# DS_zk.net
KiCad netlist of a schematic drawn in Altium Designer
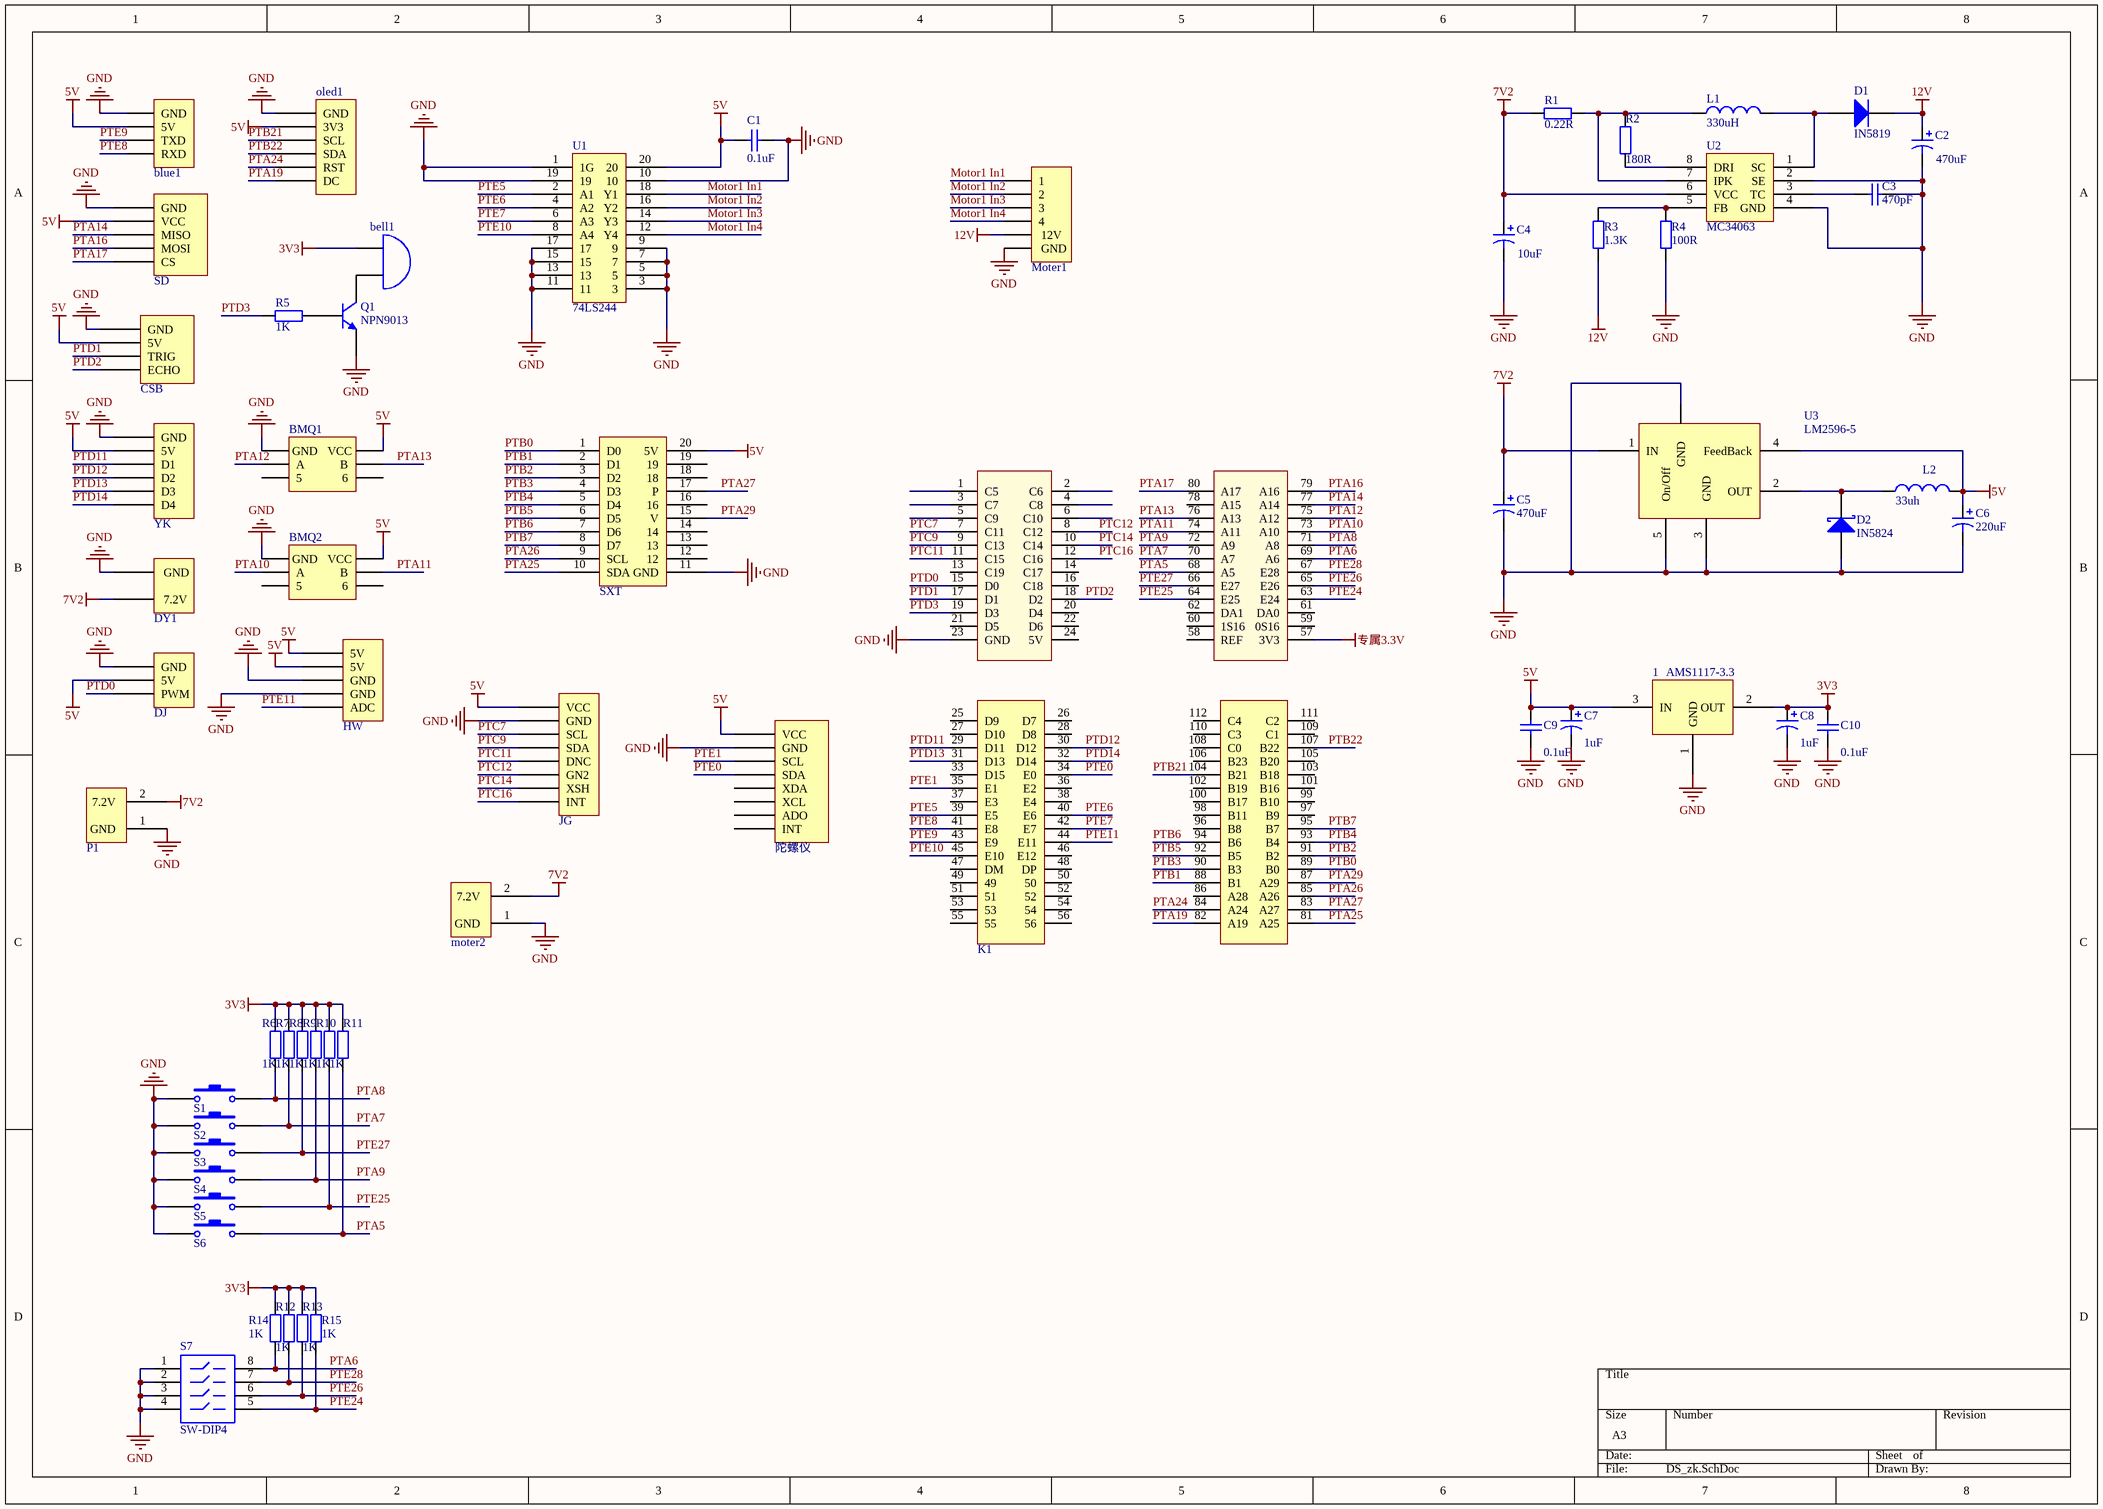
[diagram p0: DS_zk.SchDoc]

(export (version "E")
  (design (tool "Eeschema 10.0.6"))
  (components
    (comp (ref "*1") (value "SD") (footprint "HDR1X5 - duplicate") (libsource (lib "DS_zk") (part "SD卡")))
    (comp (ref "*2") (value "CSB") (footprint "HDR1X4") (libsource (lib "DS_zk") (part "超声波")))
    (comp (ref "*3") (value "YK") (footprint "HDR1X6") (libsource (lib "DS_zk") (part "遥控")))
    (comp (ref "*4") (value "SXT") (footprint "摄像头") (libsource (lib "DS_zk") (part "摄像头")))
    (comp (ref "*5") (value "HW") (footprint "HDR1X5") (libsource (lib "DS_zk") (part "红外测距")))
    (comp (ref "*6") (value "DJ") (footprint "HDR1X3") (libsource (lib "DS_zk") (part "舵机")))
    (comp (ref "*7") (value "JG") (footprint "HDR1X8") (libsource (lib "DS_zk") (part "激光")))
    (comp (ref "*8") (value "陀螺仪") (footprint "HDR1X8") (libsource (lib "DS_zk") (part "陀螺仪")))
    (comp (ref "1")
      (value "AMS1117-3.3")
      (footprint "lm1117-5v")
      (libsource (lib "红牛板Schlib") (part "LT1117-3.3"))
    )
    (comp (ref "bell1")
      (value "Bell")
      (footprint "bezzer")
      (description "Electrical Bell")
      (fields (field (name "PUBLISHER") "Altium Limited"))
      (libsource (lib "Miscellaneous Devices") (part "Bell"))
    )
    (comp (ref "blue1")
      (value "blueteeth2")
      (footprint "HDR1X4")
      (libsource (lib "DS_zk") (part "blueteeth"))
    )
    (comp (ref "BMQ1") (value "encode_1") (footprint "HDR2X3") (libsource (lib "主控板原理图") (part "encode")))
    (comp (ref "BMQ2") (value "encode_2") (footprint "HDR2X3") (libsource (lib "主控板原理图") (part "encode")))
    (comp (ref "C1")
      (value "0.1uF")
      (footprint "0603")
      (description "Capacitor (Semiconductor SIM Model)")
      (fields (field (name "PUBLISHER") "Altium Limited"))
      (libsource (lib "Miscellaneous Devices") (part "Cap Semi"))
    )
    (comp (ref "C2")
      (value "470uF")
      (footprint "470UF")
      (description "Polarized Capacitor (Surface Mount)")
      (fields (field (name "PUBLISHER") "Altium Limited"))
      (libsource (lib "Miscellaneous Devices") (part "Cap Pol3"))
    )
    (comp (ref "C3")
      (value "470pF")
      (footprint "0805")
      (description "Capacitor (Semiconductor SIM Model)")
      (fields (field (name "PUBLISHER") "Altium Limited"))
      (libsource (lib "Miscellaneous Devices") (part "Cap Semi"))
    )
    (comp (ref "C4")
      (value "10uF")
      (footprint "0805")
      (description "Polarized Capacitor (Surface Mount)")
      (fields (field (name "PUBLISHER") "Altium Limited"))
      (libsource (lib "Miscellaneous Devices") (part "Cap Pol3"))
    )
    (comp (ref "C5")
      (value "470uF")
      (footprint "470uf")
      (description "Polarized Capacitor (Radial)")
      (fields (field (name "Comment") "Cap Pol1") (field (name "PUBLISHER") "Altium Limited"))
      (libsource (lib "主控板原理图") (part "Cap Pol1"))
    )
    (comp (ref "C6")
      (value "220uF")
      (footprint "220uf")
      (description "Polarized Capacitor (Radial)")
      (fields (field (name "Comment") "Cap Pol1") (field (name "PUBLISHER") "Altium Limited"))
      (libsource (lib "主控板原理图") (part "Cap Pol1"))
    )
    (comp (ref "C7")
      (value "1uF")
      (footprint "0805")
      (description "Polarized Capacitor (Radial)")
      (fields (field (name "Comment") "Cap Pol1") (field (name "PUBLISHER") "Altium Limited"))
      (libsource (lib "Miscellaneous Devices") (part "Cap Pol1"))
    )
    (comp (ref "C8")
      (value "1uF")
      (footprint "0805")
      (description "Polarized Capacitor (Radial)")
      (fields (field (name "Comment") "Cap Pol1") (field (name "PUBLISHER") "Altium Limited"))
      (libsource (lib "Miscellaneous Devices") (part "Cap Pol1"))
    )
    (comp (ref "C9")
      (value "0.1uF")
      (footprint "0805")
      (description "Capacitor")
      (fields (field (name "Comment") "Cap") (field (name "PUBLISHER") "Altium Limited"))
      (libsource (lib "Miscellaneous Devices") (part "Cap"))
    )
    (comp (ref "C10")
      (value "0.1uF")
      (footprint "0805")
      (description "Capacitor")
      (fields (field (name "Comment") "Cap") (field (name "PUBLISHER") "Altium Limited"))
      (libsource (lib "Miscellaneous Devices") (part "Cap"))
    )
    (comp (ref "D1")
      (value "IN5819")
      (footprint "0805LED")
      (description "Default Diode")
      (fields (field (name "PUBLISHER") "Altium Limited"))
      (libsource (lib "Miscellaneous Devices") (part "Diode"))
    )
    (comp (ref "D2") (value "IN5824") (footprint "1N5824") (libsource (lib "主控板原理图") (part "IN5824")))
    (comp (ref "DY1") (value "H1") (footprint "HDR1X2") (libsource (lib "DS_zk") (part "H1")))
    (comp (ref "K1") (value "K60") (footprint "DS_K60") (libsource (lib "DS_zk") (part "K60")))
    (comp (ref "L1")
      (value "330uH")
      (footprint "电感8*8")
      (description "Inductor")
      (fields (field (name "PUBLISHER") "Altium Limited"))
      (libsource (lib "Miscellaneous Devices") (part "Inductor"))
    )
    (comp (ref "L2")
      (value "33uh")
      (footprint "电感8*8")
      (description "Inductor")
      (fields (field (name "PUBLISHER") "Altium Limited"))
      (libsource (lib "主控板原理图") (part "Inductor"))
    )
    (comp (ref "Moter1") (value "Motor") (footprint "HDR1X6") (libsource (lib "DS_zk") (part "Motor")))
    (comp (ref "moter2") (value "H1") (footprint "KF301-2P") (libsource (lib "主控板原理图") (part "H1")))
    (comp (ref "oled1") (value "OLED") (footprint "HDR1X6") (libsource (lib "LY") (part "OLED")))
    (comp (ref "P1") (value "H1") (footprint "KF301-2P") (libsource (lib "主控板原理图") (part "H1")))
    (comp (ref "Q1")
      (value "NPN9013")
      (footprint "npn9013")
      (description "NPN General Purpose Amplifier")
      (fields (field (name "PUBLISHER") "Altium Limited"))
      (libsource (lib "Miscellaneous Devices") (part "2N3904"))
    )
    (comp (ref "R1")
      (value "0.22R")
      (footprint "0805")
      (description "Resistor")
      (fields (field (name "PUBLISHER") "Altium Limited"))
      (libsource (lib "") (part "Res2_1"))
    )
    (comp (ref "R2")
      (value "180R")
      (footprint "0805")
      (description "Resistor")
      (fields (field (name "PUBLISHER") "Altium Limited"))
      (libsource (lib "Miscellaneous Devices") (part "Res2"))
    )
    (comp (ref "R3")
      (value "1.3K")
      (footprint "0805")
      (description "Resistor")
      (fields (field (name "PUBLISHER") "Altium Limited"))
      (libsource (lib "") (part "Res2_2"))
    )
    (comp (ref "R4")
      (value "100R")
      (footprint "0805")
      (description "Resistor")
      (fields (field (name "PUBLISHER") "Altium Limited"))
      (libsource (lib "") (part "Res2_2"))
    )
    (comp (ref "R5")
      (value "1K")
      (footprint "0805")
      (description "Resistor")
      (fields (field (name "Comment") "Res2") (field (name "PUBLISHER") "Altium Limited"))
      (libsource (lib "") (part "Res2_1"))
    )
    (comp (ref "R6")
      (value "1K")
      (footprint "0805")
      (description "Resistor")
      (fields (field (name "Comment") "Res2") (field (name "PUBLISHER") "Altium Limited"))
      (libsource (lib "主控板原理图") (part "Res2"))
    )
    (comp (ref "R7")
      (value "1K")
      (footprint "0805")
      (description "Resistor")
      (fields (field (name "Comment") "Res2") (field (name "PUBLISHER") "Altium Limited"))
      (libsource (lib "主控板原理图") (part "Res2"))
    )
    (comp (ref "R8")
      (value "1K")
      (footprint "0805")
      (description "Resistor")
      (fields (field (name "Comment") "Res2") (field (name "PUBLISHER") "Altium Limited"))
      (libsource (lib "主控板原理图") (part "Res2"))
    )
    (comp (ref "R9")
      (value "1K")
      (footprint "0805")
      (description "Resistor")
      (fields (field (name "Comment") "Res2") (field (name "PUBLISHER") "Altium Limited"))
      (libsource (lib "主控板原理图") (part "Res2"))
    )
    (comp (ref "R10")
      (value "1K")
      (footprint "0805")
      (description "Resistor")
      (fields (field (name "Comment") "Res2") (field (name "PUBLISHER") "Altium Limited"))
      (libsource (lib "主控板原理图") (part "Res2"))
    )
    (comp (ref "R11")
      (value "1K")
      (footprint "0805")
      (description "Resistor")
      (fields (field (name "Comment") "Res2") (field (name "PUBLISHER") "Altium Limited"))
      (libsource (lib "主控板原理图") (part "Res2"))
    )
    (comp (ref "R12")
      (value "1K")
      (footprint "0805")
      (description "Resistor")
      (fields (field (name "Comment") "Res2") (field (name "PUBLISHER") "Altium Limited"))
      (libsource (lib "主控板原理图") (part "Res2"))
    )
    (comp (ref "R13")
      (value "1K")
      (footprint "0805")
      (description "Resistor")
      (fields (field (name "Comment") "Res2") (field (name "PUBLISHER") "Altium Limited"))
      (libsource (lib "主控板原理图") (part "Res2"))
    )
    (comp (ref "R14")
      (value "1K")
      (footprint "0805")
      (description "Resistor")
      (fields (field (name "Comment") "Res2") (field (name "PUBLISHER") "Altium Limited"))
      (libsource (lib "主控板原理图") (part "Res2"))
    )
    (comp (ref "R15")
      (value "1K")
      (footprint "0805")
      (description "Resistor")
      (fields (field (name "Comment") "Res2") (field (name "PUBLISHER") "Altium Limited"))
      (libsource (lib "主控板原理图") (part "Res2"))
    )
    (comp (ref "S1")
      (value "SW-PB")
      (footprint "BUTTON")
      (description "Switch")
      (fields (field (name "PUBLISHER") "Altium Limited"))
      (libsource (lib "主控板原理图") (part "SW-PB"))
    )
    (comp (ref "S2")
      (value "SW-PB")
      (footprint "BUTTON")
      (description "Switch")
      (fields (field (name "PUBLISHER") "Altium Limited"))
      (libsource (lib "主控板原理图") (part "SW-PB"))
    )
    (comp (ref "S3")
      (value "SW-PB")
      (footprint "BUTTON")
      (description "Switch")
      (fields (field (name "PUBLISHER") "Altium Limited"))
      (libsource (lib "主控板原理图") (part "SW-PB"))
    )
    (comp (ref "S4")
      (value "SW-PB")
      (footprint "BUTTON")
      (description "Switch")
      (fields (field (name "PUBLISHER") "Altium Limited"))
      (libsource (lib "主控板原理图") (part "SW-PB"))
    )
    (comp (ref "S5")
      (value "SW-PB")
      (footprint "BUTTON")
      (description "Switch")
      (fields (field (name "PUBLISHER") "Altium Limited"))
      (libsource (lib "主控板原理图") (part "SW-PB"))
    )
    (comp (ref "S6")
      (value "SW-PB")
      (footprint "BUTTON")
      (description "Switch")
      (fields (field (name "PUBLISHER") "Altium Limited"))
      (libsource (lib "主控板原理图") (part "SW-PB"))
    )
    (comp (ref "S7")
      (value "SW-DIP4")
      (footprint "BMKG")
      (description "DIP Switch")
      (fields (field (name "PUBLISHER") "Altium Limited"))
      (libsource (lib "主控板原理图") (part "SW-DIP4"))
    )
    (comp (ref "U1") (value "74LS244") (footprint "74ls244DA") (libsource (lib "ly") (part "74LS244")))
    (comp (ref "U2") (value "MC34063") (footprint "MC34063") (libsource (lib "LY") (part "MC34063")))
    (comp (ref "U3") (value "LM2596-5") (footprint "LM2596") (libsource (lib "主控板原理图") (part "LM2596")))
  )
  (nets
    (net (code "1") (name "/Motor1 In1") (class "Default")
      (node (ref "Moter1") (pin "1") (pinfunction "1_1") (pintype "passive"))
      (node (ref "U1") (pin "18") (pinfunction "Y1_18") (pintype "passive"))
    )
    (net (code "2") (name "/Motor1 In2") (class "Default")
      (node (ref "Moter1") (pin "2") (pinfunction "2_2") (pintype "passive"))
      (node (ref "U1") (pin "16") (pinfunction "Y2_16") (pintype "passive"))
    )
    (net (code "3") (name "/Motor1 In3") (class "Default")
      (node (ref "Moter1") (pin "3") (pinfunction "3_3") (pintype "passive"))
      (node (ref "U1") (pin "14") (pinfunction "Y3_14") (pintype "passive"))
    )
    (net (code "4") (name "/Motor1 In4") (class "Default")
      (node (ref "Moter1") (pin "4") (pinfunction "4_4") (pintype "passive"))
      (node (ref "U1") (pin "12") (pinfunction "Y4_12") (pintype "passive"))
    )
    (net (code "5") (name "/PTA5") (class "Default")
      (node (ref "K1") (pin "68") (pinfunction "A5_68") (pintype "passive"))
      (node (ref "R11") (pin "1") (pinfunction "1_1") (pintype "passive"))
      (node (ref "S6") (pin "2") (pinfunction "2_2") (pintype "passive"))
    )
    (net (code "6") (name "/PTA6") (class "Default")
      (node (ref "K1") (pin "69") (pinfunction "A6_69") (pintype "passive"))
      (node (ref "R14") (pin "1") (pinfunction "1_1") (pintype "passive"))
      (node (ref "S7") (pin "8") (pinfunction "8_8") (pintype "passive"))
    )
    (net (code "7") (name "/PTA7") (class "Default")
      (node (ref "K1") (pin "70") (pinfunction "A7_70") (pintype "passive"))
      (node (ref "R7") (pin "1") (pinfunction "1_1") (pintype "passive"))
      (node (ref "S2") (pin "2") (pinfunction "2_2") (pintype "passive"))
    )
    (net (code "8") (name "/PTA8") (class "Default")
      (node (ref "K1") (pin "71") (pinfunction "A8_71") (pintype "passive"))
      (node (ref "R6") (pin "1") (pinfunction "1_1") (pintype "passive"))
      (node (ref "S1") (pin "2") (pinfunction "2_2") (pintype "passive"))
    )
    (net (code "9") (name "/PTA9") (class "Default")
      (node (ref "K1") (pin "72") (pinfunction "A9_72") (pintype "passive"))
      (node (ref "R9") (pin "1") (pinfunction "1_1") (pintype "passive"))
      (node (ref "S4") (pin "2") (pinfunction "2_2") (pintype "passive"))
    )
    (net (code "10") (name "/PTA10") (class "Default")
      (node (ref "BMQ2") (pin "3") (pinfunction "A_3") (pintype "passive"))
      (node (ref "K1") (pin "73") (pinfunction "A10_73") (pintype "passive"))
    )
    (net (code "11") (name "/PTA11") (class "Default")
      (node (ref "BMQ2") (pin "4") (pinfunction "B_4") (pintype "passive"))
      (node (ref "K1") (pin "74") (pinfunction "A11_74") (pintype "passive"))
    )
    (net (code "12") (name "/PTA12") (class "Default")
      (node (ref "BMQ1") (pin "3") (pinfunction "A_3") (pintype "passive"))
      (node (ref "K1") (pin "75") (pinfunction "A12_75") (pintype "passive"))
    )
    (net (code "13") (name "/PTA13") (class "Default")
      (node (ref "BMQ1") (pin "4") (pinfunction "B_4") (pintype "passive"))
      (node (ref "K1") (pin "76") (pinfunction "A13_76") (pintype "passive"))
    )
    (net (code "14") (name "/PTA14") (class "Default")
      (node (ref "*1") (pin "3") (pinfunction "MISO_3") (pintype "passive"))
      (node (ref "K1") (pin "77") (pinfunction "A14_77") (pintype "passive"))
    )
    (net (code "15") (name "/PTA16") (class "Default")
      (node (ref "*1") (pin "4") (pinfunction "MOSI_4") (pintype "passive"))
      (node (ref "K1") (pin "79") (pinfunction "A16_79") (pintype "passive"))
    )
    (net (code "16") (name "/PTA17") (class "Default")
      (node (ref "*1") (pin "5") (pinfunction "CS_5") (pintype "passive"))
      (node (ref "K1") (pin "80") (pinfunction "A17_80") (pintype "passive"))
    )
    (net (code "17") (name "/PTA19") (class "Default")
      (node (ref "K1") (pin "82") (pinfunction "A19_82") (pintype "passive"))
      (node (ref "oled1") (pin "6") (pinfunction "DC_6") (pintype "passive"))
    )
    (net (code "18") (name "/PTA24") (class "Default")
      (node (ref "K1") (pin "84") (pinfunction "A24_84") (pintype "passive"))
      (node (ref "oled1") (pin "5") (pinfunction "RST_5") (pintype "passive"))
    )
    (net (code "19") (name "/PTA25") (class "Default")
      (node (ref "*4") (pin "10") (pinfunction "SDA_10") (pintype "passive"))
      (node (ref "K1") (pin "81") (pinfunction "A25_81") (pintype "passive"))
    )
    (net (code "20") (name "/PTA26") (class "Default")
      (node (ref "*4") (pin "9") (pinfunction "SCL_9") (pintype "passive"))
      (node (ref "K1") (pin "85") (pinfunction "A26_85") (pintype "passive"))
    )
    (net (code "21") (name "/PTA27") (class "Default")
      (node (ref "*4") (pin "17") (pinfunction "P_17") (pintype "passive"))
      (node (ref "K1") (pin "83") (pinfunction "A27_83") (pintype "passive"))
    )
    (net (code "22") (name "/PTA29") (class "Default")
      (node (ref "*4") (pin "15") (pinfunction "V_15") (pintype "passive"))
      (node (ref "K1") (pin "87") (pinfunction "A29_87") (pintype "passive"))
    )
    (net (code "23") (name "/PTB0") (class "Default")
      (node (ref "*4") (pin "1") (pinfunction "D0_1") (pintype "passive"))
      (node (ref "K1") (pin "89") (pinfunction "B0_89") (pintype "passive"))
    )
    (net (code "24") (name "/PTB1") (class "Default")
      (node (ref "*4") (pin "2") (pinfunction "D1_2") (pintype "passive"))
      (node (ref "K1") (pin "88") (pinfunction "B1_88") (pintype "passive"))
    )
    (net (code "25") (name "/PTB2") (class "Default")
      (node (ref "*4") (pin "3") (pinfunction "D2_3") (pintype "passive"))
      (node (ref "K1") (pin "91") (pinfunction "B2_91") (pintype "passive"))
    )
    (net (code "26") (name "/PTB3") (class "Default")
      (node (ref "*4") (pin "4") (pinfunction "D3_4") (pintype "passive"))
      (node (ref "K1") (pin "90") (pinfunction "B3_90") (pintype "passive"))
    )
    (net (code "27") (name "/PTB4") (class "Default")
      (node (ref "*4") (pin "5") (pinfunction "D4_5") (pintype "passive"))
      (node (ref "K1") (pin "93") (pinfunction "B4_93") (pintype "passive"))
    )
    (net (code "28") (name "/PTB5") (class "Default")
      (node (ref "*4") (pin "6") (pinfunction "D5_6") (pintype "passive"))
      (node (ref "K1") (pin "92") (pinfunction "B5_92") (pintype "passive"))
    )
    (net (code "29") (name "/PTB6") (class "Default")
      (node (ref "*4") (pin "7") (pinfunction "D6_7") (pintype "passive"))
      (node (ref "K1") (pin "94") (pinfunction "B6_94") (pintype "passive"))
    )
    (net (code "30") (name "/PTB7") (class "Default")
      (node (ref "*4") (pin "8") (pinfunction "D7_8") (pintype "passive"))
      (node (ref "K1") (pin "95") (pinfunction "B7_95") (pintype "passive"))
    )
    (net (code "31") (name "/PTB21") (class "Default")
      (node (ref "K1") (pin "104") (pinfunction "B21_104") (pintype "passive"))
      (node (ref "oled1") (pin "3") (pinfunction "SCL_3") (pintype "passive"))
    )
    (net (code "32") (name "/PTB22") (class "Default")
      (node (ref "K1") (pin "107") (pinfunction "B22_107") (pintype "passive"))
      (node (ref "oled1") (pin "4") (pinfunction "SDA_4") (pintype "passive"))
    )
    (net (code "33") (name "/PTC7") (class "Default")
      (node (ref "*7") (pin "3") (pinfunction "SCL_3") (pintype "passive"))
      (node (ref "K1") (pin "7") (pinfunction "C11_7") (pintype "passive"))
    )
    (net (code "34") (name "/PTC9") (class "Default")
      (node (ref "*7") (pin "4") (pinfunction "SDA_4") (pintype "passive"))
      (node (ref "K1") (pin "9") (pinfunction "C13_9") (pintype "passive"))
    )
    (net (code "35") (name "/PTC11") (class "Default")
      (node (ref "*7") (pin "5") (pinfunction "DNC_5") (pintype "passive"))
      (node (ref "K1") (pin "11") (pinfunction "C15_11") (pintype "passive"))
    )
    (net (code "36") (name "/PTC12") (class "Default")
      (node (ref "*7") (pin "6") (pinfunction "GN2_6") (pintype "passive"))
      (node (ref "K1") (pin "8") (pinfunction "C12_8") (pintype "passive"))
    )
    (net (code "37") (name "/PTC14") (class "Default")
      (node (ref "*7") (pin "7") (pinfunction "XSH_7") (pintype "passive"))
      (node (ref "K1") (pin "10") (pinfunction "C14_10") (pintype "passive"))
    )
    (net (code "38") (name "/PTC16") (class "Default")
      (node (ref "*7") (pin "8") (pinfunction "INT_8") (pintype "passive"))
      (node (ref "K1") (pin "12") (pinfunction "C16_12") (pintype "passive"))
    )
    (net (code "39") (name "/PTD0") (class "Default")
      (node (ref "*6") (pin "3") (pinfunction "PWM_3") (pintype "passive"))
      (node (ref "K1") (pin "15") (pinfunction "D0_15") (pintype "passive"))
    )
    (net (code "40") (name "/PTD1") (class "Default")
      (node (ref "*2") (pin "3") (pinfunction "TRIG_3") (pintype "passive"))
      (node (ref "K1") (pin "17") (pinfunction "D1_17") (pintype "passive"))
    )
    (net (code "41") (name "/PTD2") (class "Default")
      (node (ref "*2") (pin "4") (pinfunction "ECHO_4") (pintype "passive"))
      (node (ref "K1") (pin "18") (pinfunction "D2_18") (pintype "passive"))
    )
    (net (code "42") (name "/PTD3") (class "Default")
      (node (ref "K1") (pin "19") (pinfunction "D3_19") (pintype "passive"))
      (node (ref "R5") (pin "1") (pinfunction "1_1") (pintype "passive"))
    )
    (net (code "43") (name "/PTD11") (class "Default")
      (node (ref "*3") (pin "3") (pinfunction "D1_3") (pintype "passive"))
      (node (ref "K1") (pin "29") (pinfunction "D11_29") (pintype "passive"))
    )
    (net (code "44") (name "/PTD12") (class "Default")
      (node (ref "*3") (pin "4") (pinfunction "D2_4") (pintype "passive"))
      (node (ref "K1") (pin "30") (pinfunction "D12_30") (pintype "passive"))
    )
    (net (code "45") (name "/PTD13") (class "Default")
      (node (ref "*3") (pin "5") (pinfunction "D3_5") (pintype "passive"))
      (node (ref "K1") (pin "31") (pinfunction "D13_31") (pintype "passive"))
    )
    (net (code "46") (name "/PTD14") (class "Default")
      (node (ref "*3") (pin "6") (pinfunction "D4_6") (pintype "passive"))
      (node (ref "K1") (pin "32") (pinfunction "D14_32") (pintype "passive"))
    )
    (net (code "47") (name "/PTE0") (class "Default")
      (node (ref "*8") (pin "4") (pinfunction "SDA_4") (pintype "passive"))
      (node (ref "K1") (pin "34") (pinfunction "E0_34") (pintype "passive"))
    )
    (net (code "48") (name "/PTE1") (class "Default")
      (node (ref "*8") (pin "3") (pinfunction "SCL_3") (pintype "passive"))
      (node (ref "K1") (pin "35") (pinfunction "E1_35") (pintype "passive"))
    )
    (net (code "49") (name "/PTE5") (class "Default")
      (node (ref "K1") (pin "39") (pinfunction "E5_39") (pintype "passive"))
      (node (ref "U1") (pin "2") (pinfunction "A1_2") (pintype "passive"))
    )
    (net (code "50") (name "/PTE6") (class "Default")
      (node (ref "K1") (pin "40") (pinfunction "E6_40") (pintype "passive"))
      (node (ref "U1") (pin "4") (pinfunction "A2_4") (pintype "passive"))
    )
    (net (code "51") (name "/PTE7") (class "Default")
      (node (ref "K1") (pin "42") (pinfunction "E7_42") (pintype "passive"))
      (node (ref "U1") (pin "6") (pinfunction "A3_6") (pintype "passive"))
    )
    (net (code "52") (name "/PTE8") (class "Default")
      (node (ref "K1") (pin "41") (pinfunction "E8_41") (pintype "passive"))
      (node (ref "blue1") (pin "4") (pinfunction "RXD_4") (pintype "passive"))
    )
    (net (code "53") (name "/PTE9") (class "Default")
      (node (ref "K1") (pin "43") (pinfunction "E9_43") (pintype "passive"))
      (node (ref "blue1") (pin "3") (pinfunction "TXD_3") (pintype "passive"))
    )
    (net (code "54") (name "/PTE10") (class "Default")
      (node (ref "K1") (pin "45") (pinfunction "E10_45") (pintype "passive"))
      (node (ref "U1") (pin "8") (pinfunction "A4_8") (pintype "passive"))
    )
    (net (code "55") (name "/PTE11") (class "Default")
      (node (ref "*5") (pin "5") (pinfunction "ADC_5") (pintype "passive"))
      (node (ref "K1") (pin "44") (pinfunction "E11_44") (pintype "passive"))
    )
    (net (code "56") (name "/PTE24") (class "Default")
      (node (ref "K1") (pin "63") (pinfunction "E24_63") (pintype "passive"))
      (node (ref "R15") (pin "1") (pinfunction "1_1") (pintype "passive"))
      (node (ref "S7") (pin "5") (pinfunction "5_5") (pintype "passive"))
    )
    (net (code "57") (name "/PTE25") (class "Default")
      (node (ref "K1") (pin "64") (pinfunction "E25_64") (pintype "passive"))
      (node (ref "R10") (pin "1") (pinfunction "1_1") (pintype "passive"))
      (node (ref "S5") (pin "2") (pinfunction "2_2") (pintype "passive"))
    )
    (net (code "58") (name "/PTE26") (class "Default")
      (node (ref "K1") (pin "65") (pinfunction "E26_65") (pintype "passive"))
      (node (ref "R13") (pin "1") (pinfunction "1_1") (pintype "passive"))
      (node (ref "S7") (pin "6") (pinfunction "6_6") (pintype "passive"))
    )
    (net (code "59") (name "/PTE27") (class "Default")
      (node (ref "K1") (pin "66") (pinfunction "E27_66") (pintype "passive"))
      (node (ref "R8") (pin "1") (pinfunction "1_1") (pintype "passive"))
      (node (ref "S3") (pin "2") (pinfunction "2_2") (pintype "passive"))
    )
    (net (code "60") (name "/PTE28") (class "Default")
      (node (ref "K1") (pin "67") (pinfunction "E28_67") (pintype "passive"))
      (node (ref "R12") (pin "1") (pinfunction "1_1") (pintype "passive"))
      (node (ref "S7") (pin "7") (pinfunction "7_7") (pintype "passive"))
    )
    (net (code "61") (name "3V3") (class "Default")
      (node (ref "1") (pin "2") (pinfunction "OUT_2") (pintype "open_emitter"))
      (node (ref "C10") (pin "2") (pinfunction "2_2") (pintype "passive"))
      (node (ref "C8") (pin "1") (pinfunction "1_1") (pintype "passive"))
      (node (ref "R10") (pin "2") (pinfunction "2_2") (pintype "passive"))
      (node (ref "R11") (pin "2") (pinfunction "2_2") (pintype "passive"))
      (node (ref "R12") (pin "2") (pinfunction "2_2") (pintype "passive"))
      (node (ref "R13") (pin "2") (pinfunction "2_2") (pintype "passive"))
      (node (ref "R14") (pin "2") (pinfunction "2_2") (pintype "passive"))
      (node (ref "R15") (pin "2") (pinfunction "2_2") (pintype "passive"))
      (node (ref "R6") (pin "2") (pinfunction "2_2") (pintype "passive"))
      (node (ref "R7") (pin "2") (pinfunction "2_2") (pintype "passive"))
      (node (ref "R8") (pin "2") (pinfunction "2_2") (pintype "passive"))
      (node (ref "R9") (pin "2") (pinfunction "2_2") (pintype "passive"))
      (node (ref "bell1") (pin "1") (pinfunction "A_1") (pintype "passive"))
    )
    (net (code "62") (name "5V") (class "Default")
      (node (ref "*1") (pin "2") (pinfunction "VCC_2") (pintype "passive"))
      (node (ref "*2") (pin "2") (pinfunction "5V_2") (pintype "passive"))
      (node (ref "*3") (pin "2") (pinfunction "5V_2") (pintype "passive"))
      (node (ref "*4") (pin "20") (pinfunction "5V_20") (pintype "passive"))
      (node (ref "*5") (pin "1") (pinfunction "5V_1") (pintype "passive"))
      (node (ref "*5") (pin "2") (pinfunction "5V_2") (pintype "passive"))
      (node (ref "*6") (pin "2") (pinfunction "5V_2") (pintype "passive"))
      (node (ref "*7") (pin "1") (pinfunction "VCC_1") (pintype "passive"))
      (node (ref "*8") (pin "1") (pinfunction "VCC_1") (pintype "passive"))
      (node (ref "1") (pin "3") (pinfunction "IN_3") (pintype "open_emitter"))
      (node (ref "BMQ1") (pin "2") (pinfunction "VCC_2") (pintype "passive"))
      (node (ref "BMQ2") (pin "2") (pinfunction "VCC_2") (pintype "passive"))
      (node (ref "C1") (pin "2") (pinfunction "2_2") (pintype "passive"))
      (node (ref "C6") (pin "1") (pinfunction "1_1") (pintype "passive"))
      (node (ref "C7") (pin "1") (pinfunction "1_1") (pintype "passive"))
      (node (ref "C9") (pin "2") (pinfunction "2_2") (pintype "passive"))
      (node (ref "L2") (pin "2") (pinfunction "2_2") (pintype "passive"))
      (node (ref "U1") (pin "20") (pinfunction "20_20") (pintype "passive"))
      (node (ref "U3") (pin "4") (pinfunction "FeedBack_4") (pintype "passive"))
      (node (ref "blue1") (pin "2") (pinfunction "5V_2") (pintype "passive"))
      (node (ref "oled1") (pin "2") (pinfunction "3V3_2") (pintype "passive"))
    )
    (net (code "63") (name "7V2") (class "Default")
      (node (ref "C4") (pin "1") (pinfunction "1_1") (pintype "passive"))
      (node (ref "C5") (pin "1") (pinfunction "1_1") (pintype "passive"))
      (node (ref "DY1") (pin "2") (pinfunction "7.2V_2") (pintype "passive"))
      (node (ref "P1") (pin "2") (pinfunction "7.2V_2") (pintype "passive"))
      (node (ref "R1") (pin "2") (pinfunction "2_2") (pintype "passive"))
      (node (ref "U2") (pin "6") (pinfunction "VCC_6") (pintype "passive"))
      (node (ref "U3") (pin "1") (pinfunction "IN_1") (pintype "passive"))
      (node (ref "moter2") (pin "2") (pinfunction "7.2V_2") (pintype "passive"))
    )
    (net (code "64") (name "12V") (class "Default")
      (node (ref "C2") (pin "1") (pinfunction "1_1") (pintype "passive"))
      (node (ref "D1") (pin "2") (pinfunction "K_2") (pintype "passive"))
      (node (ref "Moter1") (pin "5") (pinfunction "12V_5") (pintype "passive"))
      (node (ref "R3") (pin "2") (pinfunction "2_2") (pintype "passive"))
    )
    (net (code "65") (name "GND") (class "Default")
      (node (ref "*1") (pin "1") (pinfunction "GND_1") (pintype "passive"))
      (node (ref "*2") (pin "1") (pinfunction "GND_1") (pintype "passive"))
      (node (ref "*3") (pin "1") (pinfunction "GND_1") (pintype "passive"))
      (node (ref "*4") (pin "11") (pinfunction "GND_11") (pintype "passive"))
      (node (ref "*5") (pin "3") (pinfunction "GND_3") (pintype "passive"))
      (node (ref "*5") (pin "4") (pinfunction "GND_4") (pintype "passive"))
      (node (ref "*6") (pin "1") (pinfunction "GND_1") (pintype "passive"))
      (node (ref "*7") (pin "2") (pinfunction "GND_2") (pintype "passive"))
      (node (ref "*8") (pin "2") (pinfunction "GND_2") (pintype "passive"))
      (node (ref "1") (pin "1") (pinfunction "GND_1") (pintype "open_emitter"))
      (node (ref "BMQ1") (pin "1") (pinfunction "GND_1") (pintype "passive"))
      (node (ref "BMQ2") (pin "1") (pinfunction "GND_1") (pintype "passive"))
      (node (ref "C1") (pin "1") (pinfunction "1_1") (pintype "passive"))
      (node (ref "C10") (pin "1") (pinfunction "1_1") (pintype "passive"))
      (node (ref "C2") (pin "2") (pinfunction "2_2") (pintype "passive"))
      (node (ref "C3") (pin "2") (pinfunction "2_2") (pintype "passive"))
      (node (ref "C4") (pin "2") (pinfunction "2_2") (pintype "passive"))
      (node (ref "C5") (pin "2") (pinfunction "2_2") (pintype "passive"))
      (node (ref "C6") (pin "2") (pinfunction "2_2") (pintype "passive"))
      (node (ref "C7") (pin "2") (pinfunction "2_2") (pintype "passive"))
      (node (ref "C8") (pin "2") (pinfunction "2_2") (pintype "passive"))
      (node (ref "C9") (pin "1") (pinfunction "1_1") (pintype "passive"))
      (node (ref "D2") (pin "2") (pinfunction "K_2") (pintype "passive"))
      (node (ref "DY1") (pin "1") (pinfunction "GND_1") (pintype "passive"))
      (node (ref "K1") (pin "23") (pinfunction "GND_23") (pintype "passive"))
      (node (ref "Moter1") (pin "6") (pinfunction "GND_6") (pintype "passive"))
      (node (ref "P1") (pin "1") (pinfunction "GND_1") (pintype "passive"))
      (node (ref "Q1") (pin "1") (pinfunction "E_1") (pintype "passive"))
      (node (ref "R4") (pin "2") (pinfunction "2_2") (pintype "passive"))
      (node (ref "S1") (pin "1") (pinfunction "1_1") (pintype "passive"))
      (node (ref "S2") (pin "1") (pinfunction "1_1") (pintype "passive"))
      (node (ref "S3") (pin "1") (pinfunction "1_1") (pintype "passive"))
      (node (ref "S4") (pin "1") (pinfunction "1_1") (pintype "passive"))
      (node (ref "S5") (pin "1") (pinfunction "1_1") (pintype "passive"))
      (node (ref "S6") (pin "1") (pinfunction "1_1") (pintype "passive"))
      (node (ref "S7") (pin "1") (pinfunction "1_1") (pintype "passive"))
      (node (ref "S7") (pin "2") (pinfunction "2_2") (pintype "passive"))
      (node (ref "S7") (pin "3") (pinfunction "3_3") (pintype "passive"))
      (node (ref "S7") (pin "4") (pinfunction "4_4") (pintype "passive"))
      (node (ref "U1") (pin "1") (pinfunction "1G_1") (pintype "passive"))
      (node (ref "U1") (pin "10") (pinfunction "10_10") (pintype "passive"))
      (node (ref "U1") (pin "11") (pinfunction "11_11") (pintype "passive"))
      (node (ref "U1") (pin "13") (pinfunction "13_13") (pintype "passive"))
      (node (ref "U1") (pin "15") (pinfunction "15_15") (pintype "passive"))
      (node (ref "U1") (pin "17") (pinfunction "17_17") (pintype "passive"))
      (node (ref "U1") (pin "19") (pinfunction "19_19") (pintype "passive"))
      (node (ref "U1") (pin "3") (pinfunction "3_3") (pintype "passive"))
      (node (ref "U1") (pin "5") (pinfunction "5_5") (pintype "passive"))
      (node (ref "U1") (pin "7") (pinfunction "7_7") (pintype "passive"))
      (node (ref "U1") (pin "9") (pinfunction "9_9") (pintype "passive"))
      (node (ref "U2") (pin "2") (pinfunction "SE_2") (pintype "passive"))
      (node (ref "U2") (pin "4") (pinfunction "GND_4") (pintype "passive"))
      (node (ref "U3") (pin "3") (pinfunction "GND_3") (pintype "passive"))
      (node (ref "U3") (pin "5") (pinfunction "On/Off_5") (pintype "passive"))
      (node (ref "U3") (pin "6") (pinfunction "GND_6") (pintype "passive"))
      (node (ref "blue1") (pin "1") (pinfunction "GND_1") (pintype "passive"))
      (node (ref "moter2") (pin "1") (pinfunction "GND_1") (pintype "passive"))
      (node (ref "oled1") (pin "1") (pinfunction "GND_1") (pintype "passive"))
    )
    (net (code "66") (name "Net-(D1-A)") (class "Default")
      (node (ref "D1") (pin "1") (pinfunction "A_1") (pintype "passive"))
      (node (ref "L1") (pin "2") (pinfunction "2_2") (pintype "passive"))
      (node (ref "U2") (pin "1") (pinfunction "SC_1") (pintype "passive"))
    )
    (net (code "67") (name "Net-(D2-A)") (class "Default")
      (node (ref "D2") (pin "1") (pinfunction "A_1") (pintype "passive"))
      (node (ref "L2") (pin "1") (pinfunction "1_1") (pintype "passive"))
      (node (ref "U3") (pin "2") (pinfunction "OUT_2") (pintype "passive"))
    )
    (net (code "68") (name "Net-(Q1-B)") (class "Default")
      (node (ref "Q1") (pin "2") (pinfunction "B_2") (pintype "passive"))
      (node (ref "R5") (pin "2") (pinfunction "2_2") (pintype "passive"))
    )
    (net (code "69") (name "Net-(Q1-C)") (class "Default")
      (node (ref "Q1") (pin "3") (pinfunction "C_3") (pintype "passive"))
      (node (ref "bell1") (pin "2") (pinfunction "B_2") (pintype "passive"))
    )
    (net (code "70") (name "Net-(U2-DRI)") (class "Default")
      (node (ref "R2") (pin "1") (pinfunction "1_1") (pintype "passive"))
      (node (ref "U2") (pin "8") (pinfunction "DRI_8") (pintype "passive"))
    )
    (net (code "71") (name "Net-(U2-FB)") (class "Default")
      (node (ref "R3") (pin "1") (pinfunction "1_1") (pintype "passive"))
      (node (ref "R4") (pin "1") (pinfunction "1_1") (pintype "passive"))
      (node (ref "U2") (pin "5") (pinfunction "FB_5") (pintype "passive"))
    )
    (net (code "72") (name "Net-(U2-IPK)") (class "Default")
      (node (ref "L1") (pin "1") (pinfunction "1_1") (pintype "passive"))
      (node (ref "R1") (pin "1") (pinfunction "1_1") (pintype "passive"))
      (node (ref "R2") (pin "2") (pinfunction "2_2") (pintype "passive"))
      (node (ref "U2") (pin "7") (pinfunction "IPK_7") (pintype "passive"))
    )
    (net (code "73") (name "Net-(U2-TC)") (class "Default")
      (node (ref "C3") (pin "1") (pinfunction "1_1") (pintype "passive"))
      (node (ref "U2") (pin "3") (pinfunction "TC_3") (pintype "passive"))
    )
    (net (code "74") (name "unconnected-(*4-Pad12)") (class "Default")
      (node (ref "*4") (pin "12") (pinfunction "12_12") (pintype "passive"))
    )
    (net (code "75") (name "unconnected-(*4-Pad13)") (class "Default")
      (node (ref "*4") (pin "13") (pinfunction "13_13") (pintype "passive"))
    )
    (net (code "76") (name "unconnected-(*4-Pad14)") (class "Default")
      (node (ref "*4") (pin "14") (pinfunction "14_14") (pintype "passive"))
    )
    (net (code "77") (name "unconnected-(*4-Pad16)") (class "Default")
      (node (ref "*4") (pin "16") (pinfunction "16_16") (pintype "passive"))
    )
    (net (code "78") (name "unconnected-(*4-Pad18)") (class "Default")
      (node (ref "*4") (pin "18") (pinfunction "18_18") (pintype "passive"))
    )
    (net (code "79") (name "unconnected-(*4-Pad19)") (class "Default")
      (node (ref "*4") (pin "19") (pinfunction "19_19") (pintype "passive"))
    )
    (net (code "80") (name "unconnected-(*8-ADO-Pad7)") (class "Default")
      (node (ref "*8") (pin "7") (pinfunction "ADO_7") (pintype "passive"))
    )
    (net (code "81") (name "unconnected-(*8-INT-Pad8)") (class "Default")
      (node (ref "*8") (pin "8") (pinfunction "INT_8") (pintype "passive"))
    )
    (net (code "82") (name "unconnected-(*8-XCL-Pad6)") (class "Default")
      (node (ref "*8") (pin "6") (pinfunction "XCL_6") (pintype "passive"))
    )
    (net (code "83") (name "unconnected-(*8-XDA-Pad5)") (class "Default")
      (node (ref "*8") (pin "5") (pinfunction "XDA_5") (pintype "passive"))
    )
    (net (code "84") (name "unconnected-(BMQ1-Pad5)") (class "Default")
      (node (ref "BMQ1") (pin "5") (pinfunction "5_5") (pintype "passive"))
    )
    (net (code "85") (name "unconnected-(BMQ1-Pad6)") (class "Default")
      (node (ref "BMQ1") (pin "6") (pinfunction "6_6") (pintype "passive"))
    )
    (net (code "86") (name "unconnected-(BMQ2-Pad5)") (class "Default")
      (node (ref "BMQ2") (pin "5") (pinfunction "5_5") (pintype "passive"))
    )
    (net (code "87") (name "unconnected-(BMQ2-Pad6)") (class "Default")
      (node (ref "BMQ2") (pin "6") (pinfunction "6_6") (pintype "passive"))
    )
    (net (code "88") (name "unconnected-(K1-0S16-Pad59)") (class "Default")
      (node (ref "K1") (pin "59") (pinfunction "0S16_59") (pintype "passive"))
    )
    (net (code "89") (name "unconnected-(K1-1S16-Pad60)") (class "Default")
      (node (ref "K1") (pin "60") (pinfunction "1S16_60") (pintype "passive"))
    )
    (net (code "90") (name "unconnected-(K1-5V-Pad24)") (class "Default")
      (node (ref "K1") (pin "24") (pinfunction "5V_24") (pintype "passive"))
    )
    (net (code "91") (name "unconnected-(K1-A15-Pad78)") (class "Default")
      (node (ref "K1") (pin "78") (pinfunction "A15_78") (pintype "passive"))
    )
    (net (code "92") (name "unconnected-(K1-A28-Pad86)") (class "Default")
      (node (ref "K1") (pin "86") (pinfunction "A28_86") (pintype "passive"))
    )
    (net (code "93") (name "unconnected-(K1-B8-Pad96)") (class "Default")
      (node (ref "K1") (pin "96") (pinfunction "B8_96") (pintype "passive"))
    )
    (net (code "94") (name "unconnected-(K1-B9-Pad97)") (class "Default")
      (node (ref "K1") (pin "97") (pinfunction "B9_97") (pintype "passive"))
    )
    (net (code "95") (name "unconnected-(K1-B10-Pad99)") (class "Default")
      (node (ref "K1") (pin "99") (pinfunction "B10_99") (pintype "passive"))
    )
    (net (code "96") (name "unconnected-(K1-B11-Pad98)") (class "Default")
      (node (ref "K1") (pin "98") (pinfunction "B11_98") (pintype "passive"))
    )
    (net (code "97") (name "unconnected-(K1-B16-Pad101)") (class "Default")
      (node (ref "K1") (pin "101") (pinfunction "B16_101") (pintype "passive"))
    )
    (net (code "98") (name "unconnected-(K1-B17-Pad100)") (class "Default")
      (node (ref "K1") (pin "100") (pinfunction "B17_100") (pintype "passive"))
    )
    (net (code "99") (name "unconnected-(K1-B18-Pad103)") (class "Default")
      (node (ref "K1") (pin "103") (pinfunction "B18_103") (pintype "passive"))
    )
    (net (code "100") (name "unconnected-(K1-B19-Pad102)") (class "Default")
      (node (ref "K1") (pin "102") (pinfunction "B19_102") (pintype "passive"))
    )
    (net (code "101") (name "unconnected-(K1-B20-Pad105)") (class "Default")
      (node (ref "K1") (pin "105") (pinfunction "B20_105") (pintype "passive"))
    )
    (net (code "102") (name "unconnected-(K1-B23-Pad106)") (class "Default")
      (node (ref "K1") (pin "106") (pinfunction "B23_106") (pintype "passive"))
    )
    (net (code "103") (name "unconnected-(K1-C0-Pad108)") (class "Default")
      (node (ref "K1") (pin "108") (pinfunction "C0_108") (pintype "passive"))
    )
    (net (code "104") (name "unconnected-(K1-C1-Pad109)") (class "Default")
      (node (ref "K1") (pin "109") (pinfunction "C1_109") (pintype "passive"))
    )
    (net (code "105") (name "unconnected-(K1-C2-Pad111)") (class "Default")
      (node (ref "K1") (pin "111") (pinfunction "C2_111") (pintype "passive"))
    )
    (net (code "106") (name "unconnected-(K1-C3-Pad110)") (class "Default")
      (node (ref "K1") (pin "110") (pinfunction "C3_110") (pintype "passive"))
    )
    (net (code "107") (name "unconnected-(K1-C4-Pad112)") (class "Default")
      (node (ref "K1") (pin "112") (pinfunction "C4_112") (pintype "passive"))
    )
    (net (code "108") (name "unconnected-(K1-C5-Pad1)") (class "Default")
      (node (ref "K1") (pin "1") (pinfunction "C5_1") (pintype "passive"))
    )
    (net (code "109") (name "unconnected-(K1-C6-Pad2)") (class "Default")
      (node (ref "K1") (pin "2") (pinfunction "C6_2") (pintype "passive"))
    )
    (net (code "110") (name "unconnected-(K1-C7-Pad3)") (class "Default")
      (node (ref "K1") (pin "3") (pinfunction "C7_3") (pintype "passive"))
    )
    (net (code "111") (name "unconnected-(K1-C8-Pad4)") (class "Default")
      (node (ref "K1") (pin "4") (pinfunction "C8_4") (pintype "passive"))
    )
    (net (code "112") (name "unconnected-(K1-C9-Pad5)") (class "Default")
      (node (ref "K1") (pin "5") (pinfunction "C9_5") (pintype "passive"))
    )
    (net (code "113") (name "unconnected-(K1-C10-Pad6)") (class "Default")
      (node (ref "K1") (pin "6") (pinfunction "C10_6") (pintype "passive"))
    )
    (net (code "114") (name "unconnected-(K1-C17-Pad14)") (class "Default")
      (node (ref "K1") (pin "14") (pinfunction "C17_14") (pintype "passive"))
    )
    (net (code "115") (name "unconnected-(K1-C18-Pad16)") (class "Default")
      (node (ref "K1") (pin "16") (pinfunction "C18_16") (pintype "passive"))
    )
    (net (code "116") (name "unconnected-(K1-C19-Pad13)") (class "Default")
      (node (ref "K1") (pin "13") (pinfunction "C19_13") (pintype "passive"))
    )
    (net (code "117") (name "unconnected-(K1-D4-Pad20)") (class "Default")
      (node (ref "K1") (pin "20") (pinfunction "D4_20") (pintype "passive"))
    )
    (net (code "118") (name "unconnected-(K1-D5-Pad21)") (class "Default")
      (node (ref "K1") (pin "21") (pinfunction "D5_21") (pintype "passive"))
    )
    (net (code "119") (name "unconnected-(K1-D6-Pad22)") (class "Default")
      (node (ref "K1") (pin "22") (pinfunction "D6_22") (pintype "passive"))
    )
    (net (code "120") (name "unconnected-(K1-D7-Pad26)") (class "Default")
      (node (ref "K1") (pin "26") (pinfunction "D7_26") (pintype "passive"))
    )
    (net (code "121") (name "unconnected-(K1-D8-Pad28)") (class "Default")
      (node (ref "K1") (pin "28") (pinfunction "D8_28") (pintype "passive"))
    )
    (net (code "122") (name "unconnected-(K1-D9-Pad25)") (class "Default")
      (node (ref "K1") (pin "25") (pinfunction "D9_25") (pintype "passive"))
    )
    (net (code "123") (name "unconnected-(K1-D10-Pad27)") (class "Default")
      (node (ref "K1") (pin "27") (pinfunction "D10_27") (pintype "passive"))
    )
    (net (code "124") (name "unconnected-(K1-D15-Pad33)") (class "Default")
      (node (ref "K1") (pin "33") (pinfunction "D15_33") (pintype "passive"))
    )
    (net (code "125") (name "unconnected-(K1-DA0-Pad61)") (class "Default")
      (node (ref "K1") (pin "61") (pinfunction "DA0_61") (pintype "passive"))
    )
    (net (code "126") (name "unconnected-(K1-DA1-Pad62)") (class "Default")
      (node (ref "K1") (pin "62") (pinfunction "DA1_62") (pintype "passive"))
    )
    (net (code "127") (name "unconnected-(K1-DM-Pad47)") (class "Default")
      (node (ref "K1") (pin "47") (pinfunction "DM_47") (pintype "passive"))
    )
    (net (code "128") (name "unconnected-(K1-DP-Pad48)") (class "Default")
      (node (ref "K1") (pin "48") (pinfunction "DP_48") (pintype "passive"))
    )
    (net (code "129") (name "unconnected-(K1-E2-Pad36)") (class "Default")
      (node (ref "K1") (pin "36") (pinfunction "E2_36") (pintype "passive"))
    )
    (net (code "130") (name "unconnected-(K1-E3-Pad37)") (class "Default")
      (node (ref "K1") (pin "37") (pinfunction "E3_37") (pintype "passive"))
    )
    (net (code "131") (name "unconnected-(K1-E4-Pad38)") (class "Default")
      (node (ref "K1") (pin "38") (pinfunction "E4_38") (pintype "passive"))
    )
    (net (code "132") (name "unconnected-(K1-E12-Pad46)") (class "Default")
      (node (ref "K1") (pin "46") (pinfunction "E12_46") (pintype "passive"))
    )
    (net (code "133") (name "unconnected-(K1-Pad49)") (class "Default")
      (node (ref "K1") (pin "49") (pinfunction "49_49") (pintype "passive"))
    )
    (net (code "134") (name "unconnected-(K1-Pad50)") (class "Default")
      (node (ref "K1") (pin "50") (pinfunction "50_50") (pintype "passive"))
    )
    (net (code "135") (name "unconnected-(K1-Pad51)") (class "Default")
      (node (ref "K1") (pin "51") (pinfunction "51_51") (pintype "passive"))
    )
    (net (code "136") (name "unconnected-(K1-Pad52)") (class "Default")
      (node (ref "K1") (pin "52") (pinfunction "52_52") (pintype "passive"))
    )
    (net (code "137") (name "unconnected-(K1-Pad53)") (class "Default")
      (node (ref "K1") (pin "53") (pinfunction "53_53") (pintype "passive"))
    )
    (net (code "138") (name "unconnected-(K1-Pad54)") (class "Default")
      (node (ref "K1") (pin "54") (pinfunction "54_54") (pintype "passive"))
    )
    (net (code "139") (name "unconnected-(K1-Pad55)") (class "Default")
      (node (ref "K1") (pin "55") (pinfunction "55_55") (pintype "passive"))
    )
    (net (code "140") (name "unconnected-(K1-Pad56)") (class "Default")
      (node (ref "K1") (pin "56") (pinfunction "56_56") (pintype "passive"))
    )
    (net (code "141") (name "unconnected-(K1-REF-Pad58)") (class "Default")
      (node (ref "K1") (pin "58") (pinfunction "REF_58") (pintype "passive"))
    )
    (net (code "142") (name "专属3.3V") (class "Default")
      (node (ref "K1") (pin "57") (pinfunction "3V3_57") (pintype "passive"))
    )
  )
)
